# STM8_remote.net
KiCad netlist of a schematic drawn in Altium Designer
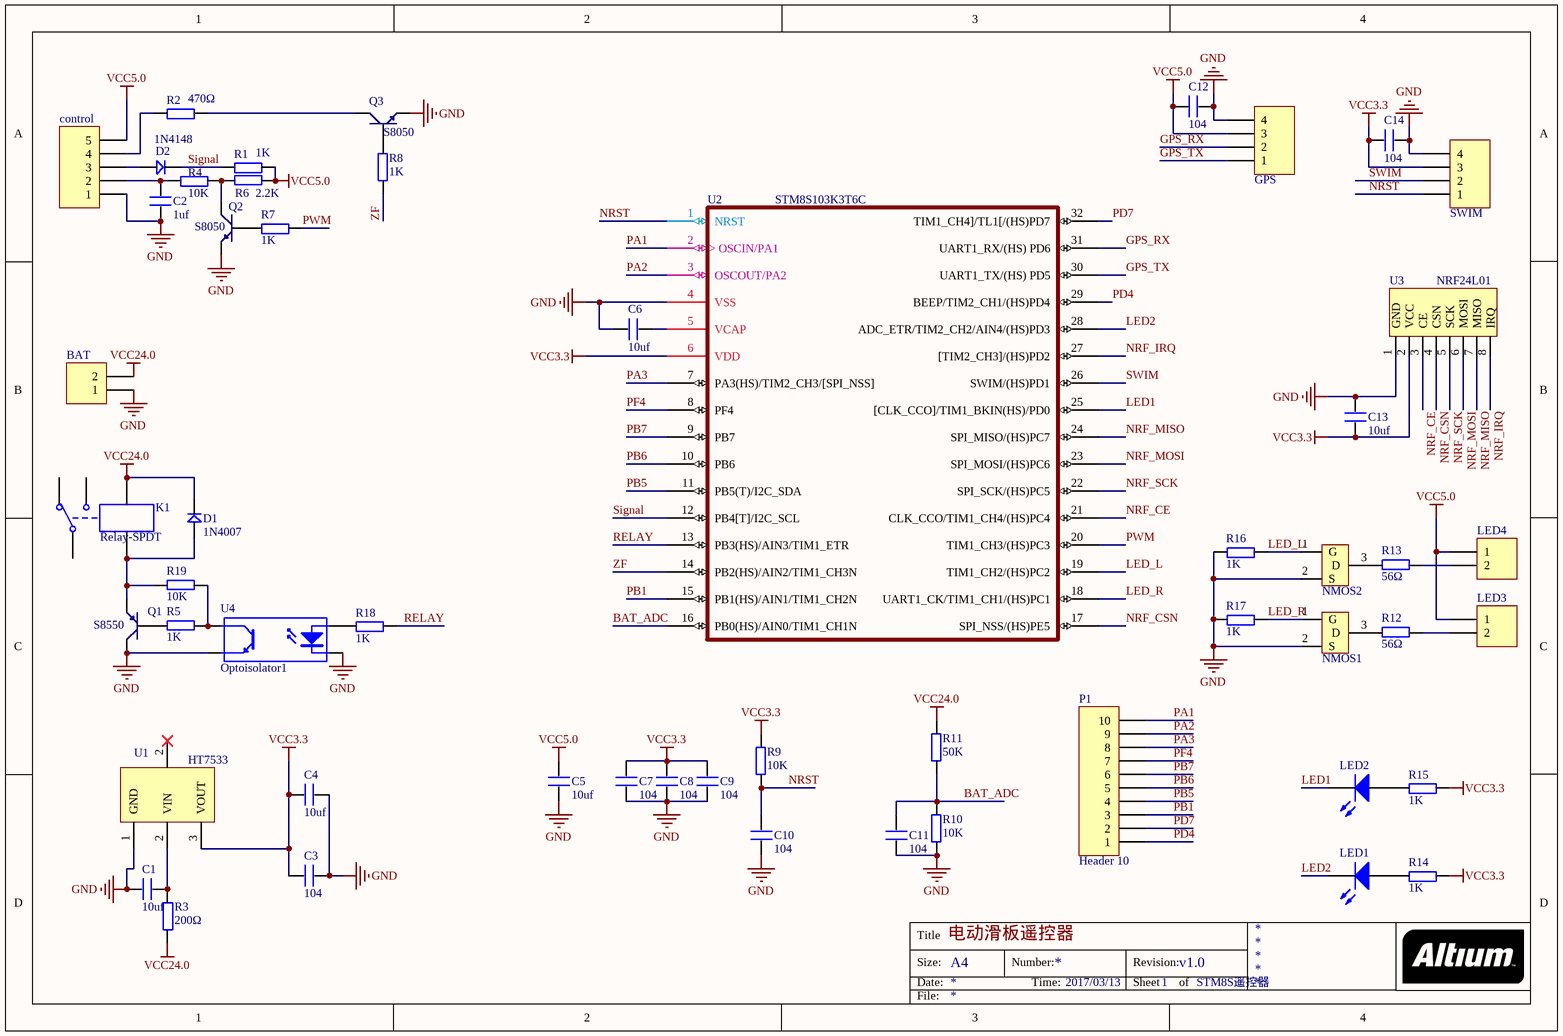
[diagram p0: STM8_remote.SchDoc]

(export (version "E")
  (design (tool "Eeschema 10.0.6"))
  (components
    (comp (ref "BAT")
      (value "Header 2")
      (footprint "HDR1X2")
      (description "Header, 2-Pin")
      (fields (field (name "PUBLISHER") "Altium Limited"))
      (libsource (lib "") (part "Header 2_1"))
    )
    (comp (ref "C1") (value "10uf") (footprint "tantalum capacitors") (libsource (lib "EXPLORER") (part "C")))
    (comp (ref "C2") (value "1uf") (footprint "0603P") (libsource (lib "EXPLORER") (part "C")))
    (comp (ref "C3") (value "104") (footprint "0603P") (libsource (lib "EXPLORER") (part "C")))
    (comp (ref "C4") (value "10uf") (footprint "tantalum capacitors") (libsource (lib "EXPLORER") (part "C")))
    (comp (ref "C5") (value "10uf") (footprint "tantalum capacitors") (libsource (lib "EXPLORER") (part "C")))
    (comp (ref "C6") (value "10uf") (footprint "0805") (libsource (lib "EXPLORER") (part "C")))
    (comp (ref "C7") (value "104") (footprint "0603P") (libsource (lib "EXPLORER") (part "C")))
    (comp (ref "C8") (value "104") (footprint "0603P") (libsource (lib "EXPLORER") (part "C")))
    (comp (ref "C9") (value "104") (footprint "0603P") (libsource (lib "EXPLORER") (part "C")))
    (comp (ref "C10") (value "104") (footprint "0603P") (libsource (lib "EXPLORER") (part "C")))
    (comp (ref "C11") (value "104") (footprint "0603P") (libsource (lib "EXPLORER") (part "C")))
    (comp (ref "C12") (value "104") (footprint "0603P") (libsource (lib "EXPLORER") (part "C")))
    (comp (ref "C13")
      (value "10uf")
      (footprint "tantalum capacitors")
      (libsource (lib "EXPLORER") (part "C"))
    )
    (comp (ref "C14") (value "104") (footprint "0603P") (libsource (lib "EXPLORER") (part "C")))
    (comp (ref "control")
      (value "Header 5")
      (footprint "HDR1X5")
      (description "Header, 5-Pin")
      (fields (field (name "PUBLISHER") "Altium Limited"))
      (libsource (lib "Miscellaneous Connectors") (part "Header 5"))
    )
    (comp (ref "D1") (value "1N4007") (footprint "DIODE_3*5.3") (libsource (lib "EXPLORER") (part "D")))
    (comp (ref "D2") (value "1N4148") (footprint "0603P") (libsource (lib "EXPLORER") (part "D")))
    (comp (ref "GPS")
      (value "Header 4")
      (footprint "HDR1X4")
      (description "Header, 4-Pin")
      (fields (field (name "PUBLISHER") "Altium Limited"))
      (libsource (lib "EXPLORER") (part "Header 4"))
    )
    (comp (ref "K1")
      (value "Relay-SPDT")
      (footprint "RELAY")
      (description "Single-Pole Dual-Throw Relay")
      (fields (field (name "PUBLISHER") "Altium Limited"))
      (libsource (lib "Miscellaneous Devices") (part "Relay-SPDT"))
    )
    (comp (ref "LED1")
      (value "LED1")
      (footprint "SMDLED")
      (description "Typical RED, GREEN, YELLOW, AMBER GaAs LED")
      (fields (field (name "PUBLISHER") "Altium Limited"))
      (libsource (lib "EXPLORER") (part "LED2"))
    )
    (comp (ref "LED2")
      (value "LED1")
      (footprint "SMDLED")
      (description "Typical RED, GREEN, YELLOW, AMBER GaAs LED")
      (fields (field (name "PUBLISHER") "Altium Limited"))
      (libsource (lib "EXPLORER") (part "LED2"))
    )
    (comp (ref "LED3")
      (value "Header 2")
      (footprint "HDR1X2")
      (description "Header, 2-Pin")
      (fields (field (name "PUBLISHER") "Altium Limited"))
      (libsource (lib "Miscellaneous Connectors") (part "Header 2"))
    )
    (comp (ref "LED4")
      (value "Header 2")
      (footprint "HDR1X2")
      (description "Header, 2-Pin")
      (fields (field (name "PUBLISHER") "Altium Limited"))
      (libsource (lib "Miscellaneous Connectors") (part "Header 2"))
    )
    (comp (ref "NMOS1")
      (value "SI2301")
      (footprint "SO-G3/C2.5")
      (description "IRLML6401/SI2301")
      (libsource (lib "EXPLORER") (part "MOS-P"))
    )
    (comp (ref "NMOS2")
      (value "SI2301")
      (footprint "SO-G3/C2.5")
      (description "IRLML6401/SI2301")
      (libsource (lib "EXPLORER") (part "MOS-P"))
    )
    (comp (ref "P1")
      (value "Header 10")
      (footprint "HDR1X10")
      (description "Header, 10-Pin")
      (fields (field (name "PUBLISHER") "Altium Limited"))
      (libsource (lib "Miscellaneous Connectors") (part "Header 10"))
    )
    (comp (ref "Q1")
      (value "S8550")
      (footprint "SOT-23R")
      (description "8550/BCW68")
      (libsource (lib "EXPLORER") (part "PNP"))
    )
    (comp (ref "Q2")
      (value "S8050")
      (footprint "SOT-23R")
      (description "8050/BCW846/BCW847")
      (libsource (lib "EXPLORER") (part "NPN"))
    )
    (comp (ref "Q3")
      (value "S8050")
      (footprint "SOT-23R")
      (description "8050/BCW846/BCW847")
      (libsource (lib "EXPLORER") (part "NPN"))
    )
    (comp (ref "R1") (value "1K") (footprint "0603P") (libsource (lib "EXPLORER") (part "R")))
    (comp (ref "R2") (value "470Ω") (footprint "0603P") (libsource (lib "EXPLORER") (part "R")))
    (comp (ref "R3") (value "200Ω") (footprint "0603P") (libsource (lib "EXPLORER") (part "R")))
    (comp (ref "R4") (value "10K") (footprint "0603P") (libsource (lib "EXPLORER") (part "R")))
    (comp (ref "R5") (value "1K") (footprint "0603P") (libsource (lib "EXPLORER") (part "R")))
    (comp (ref "R6") (value "2.2K") (footprint "0603P") (libsource (lib "EXPLORER") (part "R")))
    (comp (ref "R7") (value "1K") (footprint "0603P") (libsource (lib "EXPLORER") (part "R")))
    (comp (ref "R8") (value "1K") (footprint "0603P") (libsource (lib "EXPLORER") (part "R")))
    (comp (ref "R9") (value "10K") (footprint "0603P") (libsource (lib "EXPLORER") (part "R")))
    (comp (ref "R10") (value "10K") (footprint "0603P") (libsource (lib "EXPLORER") (part "R")))
    (comp (ref "R11") (value "50K") (footprint "0603P") (libsource (lib "EXPLORER") (part "R")))
    (comp (ref "R12") (value "56Ω") (footprint "0805") (libsource (lib "EXPLORER") (part "R")))
    (comp (ref "R13") (value "56Ω") (footprint "0805") (libsource (lib "EXPLORER") (part "R")))
    (comp (ref "R14") (value "1K") (footprint "0603P") (libsource (lib "EXPLORER") (part "R")))
    (comp (ref "R15") (value "1K") (footprint "0603P") (libsource (lib "EXPLORER") (part "R")))
    (comp (ref "R16") (value "1K") (footprint "0603P") (libsource (lib "EXPLORER") (part "R")))
    (comp (ref "R17") (value "1K") (footprint "0603P") (libsource (lib "EXPLORER") (part "R")))
    (comp (ref "R18") (value "1K") (footprint "0603P") (libsource (lib "EXPLORER") (part "R")))
    (comp (ref "R19") (value "10K") (footprint "0603P") (libsource (lib "EXPLORER") (part "R")))
    (comp (ref "SWIM")
      (value "Header 4")
      (footprint "HDR1X4")
      (description "Header, 4-Pin")
      (fields (field (name "PUBLISHER") "Altium Limited"))
      (libsource (lib "EXPLORER") (part "Header 4"))
    )
    (comp (ref "U1") (value "HT7533") (footprint "SOT-89") (libsource (lib "*") (part "HT75xx")))
    (comp (ref "U2")
      (value "STM8S103K3T6C")
      (footprint "TQFP32")
      (description "ST 8-bit  Microcontroller")
      (libsource (lib "STMicrocontroller 8") (part "STM8S103K3T6"))
    )
    (comp (ref "U3") (value "NRF24L01") (footprint "NRF24L01") (libsource (lib "EXPLORER") (part "NRF24L01")))
    (comp (ref "U4")
      (value "Optoisolator1")
      (footprint "DIP-4")
      (description "4-Pin Phototransistor Optocoupler")
      (fields (field (name "PUBLISHER") "Altium Limited"))
      (libsource (lib "Miscellaneous Devices") (part "Optoisolator1"))
    )
  )
  (nets
    (net (code "1") (name "/BAT_ADC") (class "Default")
      (node (ref "C11") (pin "2") (pintype "passive"))
      (node (ref "R10") (pin "1") (pintype "passive"))
      (node (ref "R11") (pin "2") (pintype "passive"))
      (node (ref "U2") (pin "16") (pinfunction "PB0(HS)/AIN0/TIM1_CH1N_16") (pintype "bidirectional"))
    )
    (net (code "2") (name "/GPS_RX") (class "Default")
      (node (ref "GPS") (pin "2") (pinfunction "2_2") (pintype "passive"))
      (node (ref "U2") (pin "31") (pinfunction "UART1_RX/(HS)_PD6_31") (pintype "bidirectional"))
    )
    (net (code "3") (name "/GPS_TX") (class "Default")
      (node (ref "GPS") (pin "1") (pinfunction "1_1") (pintype "passive"))
      (node (ref "U2") (pin "30") (pinfunction "UART1_TX/(HS)_PD5_30") (pintype "bidirectional"))
    )
    (net (code "4") (name "/LED1") (class "Default")
      (node (ref "LED2") (pin "2") (pinfunction "K_2") (pintype "passive"))
      (node (ref "U2") (pin "25") (pinfunction "[CLK_CCO]/TIM1_BKIN(HS)/PD0_25") (pintype "bidirectional"))
    )
    (net (code "5") (name "/LED2") (class "Default")
      (node (ref "LED1") (pin "2") (pinfunction "K_2") (pintype "passive"))
      (node (ref "U2") (pin "28") (pinfunction "ADC_ETR/TIM2_CH2/AIN4/(HS)PD3_28") (pintype "bidirectional"))
    )
    (net (code "6") (name "/LED_L") (class "Default")
      (node (ref "NMOS2") (pin "1") (pinfunction "G_1") (pintype "passive"))
      (node (ref "R16") (pin "2") (pintype "passive"))
      (node (ref "U2") (pin "19") (pinfunction "TIM1_CH2/(HS)PC2_19") (pintype "bidirectional"))
    )
    (net (code "7") (name "/LED_R") (class "Default")
      (node (ref "NMOS1") (pin "1") (pinfunction "G_1") (pintype "passive"))
      (node (ref "R17") (pin "2") (pintype "passive"))
      (node (ref "U2") (pin "18") (pinfunction "UART1_CK/TIM1_CH1/(HS)PC1_18") (pintype "bidirectional"))
    )
    (net (code "8") (name "/NRF_CE") (class "Default")
      (node (ref "U2") (pin "21") (pinfunction "CLK_CCO/TIM1_CH4/(HS)PC4_21") (pintype "bidirectional"))
      (node (ref "U3") (pin "3") (pinfunction "CE_3") (pintype "passive"))
    )
    (net (code "9") (name "/NRF_CSN") (class "Default")
      (node (ref "U2") (pin "17") (pinfunction "SPI_NSS/(HS)PE5_17") (pintype "bidirectional"))
      (node (ref "U3") (pin "4") (pinfunction "CSN_4") (pintype "passive"))
    )
    (net (code "10") (name "/NRF_IRQ") (class "Default")
      (node (ref "U2") (pin "27") (pinfunction "[TIM2_CH3]/(HS)PD2_27") (pintype "bidirectional"))
      (node (ref "U3") (pin "8") (pinfunction "IRQ_8") (pintype "passive"))
    )
    (net (code "11") (name "/NRF_MISO") (class "Default")
      (node (ref "U2") (pin "24") (pinfunction "SPI_MISO/(HS)PC7_24") (pintype "bidirectional"))
      (node (ref "U3") (pin "7") (pinfunction "MISO_7") (pintype "passive"))
    )
    (net (code "12") (name "/NRF_MOSI") (class "Default")
      (node (ref "U2") (pin "23") (pinfunction "SPI_MOSI/(HS)PC6_23") (pintype "bidirectional"))
      (node (ref "U3") (pin "6") (pinfunction "MOSI_6") (pintype "passive"))
    )
    (net (code "13") (name "/NRF_SCK") (class "Default")
      (node (ref "U2") (pin "22") (pinfunction "SPI_SCK/(HS)PC5_22") (pintype "bidirectional"))
      (node (ref "U3") (pin "5") (pinfunction "SCK_5") (pintype "passive"))
    )
    (net (code "14") (name "/NRST") (class "Default")
      (node (ref "C10") (pin "2") (pintype "passive"))
      (node (ref "R9") (pin "2") (pintype "passive"))
      (node (ref "SWIM") (pin "1") (pinfunction "1_1") (pintype "passive"))
      (node (ref "U2") (pin "1") (pinfunction "NRST_1") (pintype "bidirectional"))
    )
    (net (code "15") (name "/PA1") (class "Default")
      (node (ref "P1") (pin "10") (pinfunction "10_10") (pintype "passive"))
      (node (ref "U2") (pin "2") (pinfunction "OSCIN/PA1_2") (pintype "bidirectional"))
    )
    (net (code "16") (name "/PA2") (class "Default")
      (node (ref "P1") (pin "9") (pinfunction "9_9") (pintype "passive"))
      (node (ref "U2") (pin "3") (pinfunction "OSCOUT/PA2_3") (pintype "bidirectional"))
    )
    (net (code "17") (name "/PA3") (class "Default")
      (node (ref "P1") (pin "8") (pinfunction "8_8") (pintype "passive"))
      (node (ref "U2") (pin "7") (pinfunction "PA3(HS)/TIM2_CH3/[SPI_NSS]_7") (pintype "bidirectional"))
    )
    (net (code "18") (name "/PB1") (class "Default")
      (node (ref "P1") (pin "3") (pinfunction "3_3") (pintype "passive"))
      (node (ref "U2") (pin "15") (pinfunction "PB1(HS)/AIN1/TIM1_CH2N_15") (pintype "bidirectional"))
    )
    (net (code "19") (name "/PB5") (class "Default")
      (node (ref "P1") (pin "4") (pinfunction "4_4") (pintype "passive"))
      (node (ref "U2") (pin "11") (pinfunction "PB5(T)/I2C_SDA_11") (pintype "bidirectional"))
    )
    (net (code "20") (name "/PB6") (class "Default")
      (node (ref "P1") (pin "5") (pinfunction "5_5") (pintype "passive"))
      (node (ref "U2") (pin "10") (pinfunction "PB6_10") (pintype "bidirectional"))
    )
    (net (code "21") (name "/PB7") (class "Default")
      (node (ref "P1") (pin "6") (pinfunction "6_6") (pintype "passive"))
      (node (ref "U2") (pin "9") (pinfunction "PB7_9") (pintype "bidirectional"))
    )
    (net (code "22") (name "/PD4") (class "Default")
      (node (ref "P1") (pin "1") (pinfunction "1_1") (pintype "passive"))
      (node (ref "U2") (pin "29") (pinfunction "BEEP/TIM2_CH1/(HS)PD4_29") (pintype "bidirectional"))
    )
    (net (code "23") (name "/PD7") (class "Default")
      (node (ref "P1") (pin "2") (pinfunction "2_2") (pintype "passive"))
      (node (ref "U2") (pin "32") (pinfunction "TIM1_CH4]/TL1[/(HS)PD7_32") (pintype "bidirectional"))
    )
    (net (code "24") (name "/PF4") (class "Default")
      (node (ref "P1") (pin "7") (pinfunction "7_7") (pintype "passive"))
      (node (ref "U2") (pin "8") (pinfunction "PF4_8") (pintype "bidirectional"))
    )
    (net (code "25") (name "/PWM") (class "Default")
      (node (ref "R7") (pin "2") (pintype "passive"))
      (node (ref "U2") (pin "20") (pinfunction "TIM1_CH3/(HS)PC3_20") (pintype "bidirectional"))
    )
    (net (code "26") (name "/RELAY") (class "Default")
      (node (ref "R18") (pin "2") (pintype "passive"))
      (node (ref "U2") (pin "13") (pinfunction "PB3(HS)/AIN3/TIM1_ETR_13") (pintype "bidirectional"))
    )
    (net (code "27") (name "/SWIM") (class "Default")
      (node (ref "SWIM") (pin "2") (pinfunction "2_2") (pintype "passive"))
      (node (ref "U2") (pin "26") (pinfunction "SWIM/(HS)PD1_26") (pintype "bidirectional"))
    )
    (net (code "28") (name "/Signal") (class "Default")
      (node (ref "D2") (pin "2") (pintype "passive"))
      (node (ref "R1") (pin "1") (pintype "passive"))
      (node (ref "U2") (pin "12") (pinfunction "PB4[T]/I2C_SCL_12") (pintype "bidirectional"))
    )
    (net (code "29") (name "/ZF") (class "Default")
      (node (ref "R8") (pin "2") (pintype "passive"))
      (node (ref "U2") (pin "14") (pinfunction "PB2(HS)/AIN2/TIM1_CH3N_14") (pintype "bidirectional"))
    )
    (net (code "30") (name "GND") (class "Default")
      (node (ref "BAT") (pin "1") (pinfunction "1_1") (pintype "passive"))
      (node (ref "C1") (pin "1") (pintype "passive"))
      (node (ref "C10") (pin "1") (pintype "passive"))
      (node (ref "C11") (pin "1") (pintype "passive"))
      (node (ref "C12") (pin "2") (pintype "passive"))
      (node (ref "C13") (pin "1") (pintype "passive"))
      (node (ref "C14") (pin "2") (pintype "passive"))
      (node (ref "C2") (pin "1") (pintype "passive"))
      (node (ref "C3") (pin "1") (pintype "passive"))
      (node (ref "C4") (pin "1") (pintype "passive"))
      (node (ref "C5") (pin "1") (pintype "passive"))
      (node (ref "C6") (pin "1") (pintype "passive"))
      (node (ref "C7") (pin "1") (pintype "passive"))
      (node (ref "C8") (pin "1") (pintype "passive"))
      (node (ref "C9") (pin "1") (pintype "passive"))
      (node (ref "GPS") (pin "4") (pinfunction "4_4") (pintype "passive"))
      (node (ref "NMOS1") (pin "2") (pinfunction "S_2") (pintype "passive"))
      (node (ref "NMOS2") (pin "2") (pinfunction "S_2") (pintype "passive"))
      (node (ref "Q1") (pin "3") (pinfunction "C_3") (pintype "passive"))
      (node (ref "Q2") (pin "1") (pinfunction "E_1") (pintype "passive"))
      (node (ref "Q3") (pin "1") (pinfunction "E_1") (pintype "passive"))
      (node (ref "R10") (pin "2") (pintype "passive"))
      (node (ref "R16") (pin "1") (pintype "passive"))
      (node (ref "R17") (pin "1") (pintype "passive"))
      (node (ref "SWIM") (pin "4") (pinfunction "4_4") (pintype "passive"))
      (node (ref "U1") (pin "1") (pinfunction "GND_1") (pintype "passive"))
      (node (ref "U2") (pin "4") (pinfunction "VSS_4") (pintype "power_in"))
      (node (ref "U3") (pin "1") (pinfunction "GND_1") (pintype "passive"))
      (node (ref "U4") (pin "2") (pinfunction "K_2") (pintype "passive"))
      (node (ref "U4") (pin "3") (pinfunction "E_3") (pintype "passive"))
      (node (ref "control") (pin "1") (pinfunction "1_1") (pintype "passive"))
    )
    (net (code "31") (name "Net-(C2-Pad2)") (class "Default")
      (node (ref "C2") (pin "2") (pintype "passive"))
      (node (ref "R4") (pin "1") (pintype "passive"))
      (node (ref "control") (pin "2") (pinfunction "2_2") (pintype "passive"))
    )
    (net (code "32") (name "Net-(D2-Pad1)") (class "Default")
      (node (ref "D2") (pin "1") (pintype "passive"))
      (node (ref "control") (pin "3") (pinfunction "3_3") (pintype "passive"))
    )
    (net (code "33") (name "Net-(LED1-A)") (class "Default")
      (node (ref "LED1") (pin "1") (pinfunction "A_1") (pintype "passive"))
      (node (ref "R14") (pin "1") (pintype "passive"))
    )
    (net (code "34") (name "Net-(LED2-A)") (class "Default")
      (node (ref "LED2") (pin "1") (pinfunction "A_1") (pintype "passive"))
      (node (ref "R15") (pin "1") (pintype "passive"))
    )
    (net (code "35") (name "Net-(LED3-Pad2)") (class "Default")
      (node (ref "LED3") (pin "2") (pinfunction "2_2") (pintype "passive"))
      (node (ref "R12") (pin "1") (pintype "passive"))
    )
    (net (code "36") (name "Net-(LED4-Pad2)") (class "Default")
      (node (ref "LED4") (pin "2") (pinfunction "2_2") (pintype "passive"))
      (node (ref "R13") (pin "1") (pintype "passive"))
    )
    (net (code "37") (name "Net-(NMOS1-D)") (class "Default")
      (node (ref "NMOS1") (pin "3") (pinfunction "D_3") (pintype "passive"))
      (node (ref "R12") (pin "2") (pintype "passive"))
    )
    (net (code "38") (name "Net-(NMOS2-D)") (class "Default")
      (node (ref "NMOS2") (pin "3") (pinfunction "D_3") (pintype "passive"))
      (node (ref "R13") (pin "2") (pintype "passive"))
    )
    (net (code "39") (name "Net-(Q1-B)") (class "Default")
      (node (ref "Q1") (pin "2") (pinfunction "B_2") (pintype "passive"))
      (node (ref "R5") (pin "2") (pintype "passive"))
    )
    (net (code "40") (name "Net-(Q1-E)") (class "Default")
      (node (ref "D1") (pin "1") (pintype "passive"))
      (node (ref "K1") (pin "4") (pinfunction "4_4") (pintype "passive"))
      (node (ref "Q1") (pin "1") (pinfunction "E_1") (pintype "passive"))
      (node (ref "R19") (pin "2") (pintype "passive"))
    )
    (net (code "41") (name "Net-(Q2-B)") (class "Default")
      (node (ref "Q2") (pin "2") (pinfunction "B_2") (pintype "passive"))
      (node (ref "R7") (pin "1") (pintype "passive"))
    )
    (net (code "42") (name "Net-(Q2-C)") (class "Default")
      (node (ref "Q2") (pin "3") (pinfunction "C_3") (pintype "passive"))
      (node (ref "R4") (pin "2") (pintype "passive"))
      (node (ref "R6") (pin "2") (pintype "passive"))
    )
    (net (code "43") (name "Net-(Q3-B)") (class "Default")
      (node (ref "Q3") (pin "2") (pinfunction "B_2") (pintype "passive"))
      (node (ref "R8") (pin "1") (pintype "passive"))
    )
    (net (code "44") (name "Net-(Q3-C)") (class "Default")
      (node (ref "Q3") (pin "3") (pinfunction "C_3") (pintype "passive"))
      (node (ref "R2") (pin "2") (pintype "passive"))
    )
    (net (code "45") (name "Net-(R2-Pad1)") (class "Default")
      (node (ref "R2") (pin "1") (pintype "passive"))
      (node (ref "control") (pin "4") (pinfunction "4_4") (pintype "passive"))
    )
    (net (code "46") (name "Net-(U1-VIN)") (class "Default")
      (node (ref "C1") (pin "2") (pintype "passive"))
      (node (ref "R3") (pin "2") (pintype "passive"))
      (node (ref "U1") (pin "2") (pinfunction "VIN_2") (pintype "passive"))
    )
    (net (code "47") (name "Net-(U2-VCAP)") (class "Default")
      (node (ref "C6") (pin "2") (pintype "passive"))
      (node (ref "U2") (pin "5") (pinfunction "VCAP_5") (pintype "power_in"))
    )
    (net (code "48") (name "Net-(U4-A)") (class "Default")
      (node (ref "R18") (pin "1") (pintype "passive"))
      (node (ref "U4") (pin "1") (pinfunction "A_1") (pintype "passive"))
    )
    (net (code "49") (name "Net-(U4-C)") (class "Default")
      (node (ref "R19") (pin "1") (pintype "passive"))
      (node (ref "R5") (pin "1") (pintype "passive"))
      (node (ref "U4") (pin "4") (pinfunction "C_4") (pintype "passive"))
    )
    (net (code "50") (name "VCC3.3") (class "Default")
      (node (ref "C13") (pin "2") (pintype "passive"))
      (node (ref "C14") (pin "1") (pintype "passive"))
      (node (ref "C3") (pin "2") (pintype "passive"))
      (node (ref "C4") (pin "2") (pintype "passive"))
      (node (ref "C7") (pin "2") (pintype "passive"))
      (node (ref "C8") (pin "2") (pintype "passive"))
      (node (ref "C9") (pin "2") (pintype "passive"))
      (node (ref "R14") (pin "2") (pintype "passive"))
      (node (ref "R15") (pin "2") (pintype "passive"))
      (node (ref "R9") (pin "1") (pintype "passive"))
      (node (ref "SWIM") (pin "3") (pinfunction "3_3") (pintype "passive"))
      (node (ref "U1") (pin "3") (pinfunction "VOUT_3") (pintype "passive"))
      (node (ref "U2") (pin "6") (pinfunction "VDD_6") (pintype "power_in"))
      (node (ref "U3") (pin "2") (pinfunction "VCC_2") (pintype "passive"))
    )
    (net (code "51") (name "VCC5.0") (class "Default")
      (node (ref "C12") (pin "1") (pintype "passive"))
      (node (ref "C5") (pin "2") (pintype "passive"))
      (node (ref "GPS") (pin "3") (pinfunction "3_3") (pintype "passive"))
      (node (ref "LED3") (pin "1") (pinfunction "1_1") (pintype "passive"))
      (node (ref "LED4") (pin "1") (pinfunction "1_1") (pintype "passive"))
      (node (ref "R1") (pin "2") (pintype "passive"))
      (node (ref "R6") (pin "1") (pintype "passive"))
      (node (ref "control") (pin "5") (pinfunction "5_5") (pintype "passive"))
    )
    (net (code "52") (name "VCC24.0") (class "Default")
      (node (ref "BAT") (pin "2") (pinfunction "2_2") (pintype "passive"))
      (node (ref "D1") (pin "2") (pintype "passive"))
      (node (ref "K1") (pin "5") (pinfunction "5_5") (pintype "passive"))
      (node (ref "R11") (pin "1") (pintype "passive"))
      (node (ref "R3") (pin "1") (pintype "passive"))
    )
    (net (code "53") (name "unconnected-(K1-Pad1)") (class "Default")
      (node (ref "K1") (pin "1") (pinfunction "1_1") (pintype "passive"))
    )
    (net (code "54") (name "unconnected-(K1-Pad2)") (class "Default")
      (node (ref "K1") (pin "2") (pinfunction "2_2") (pintype "passive"))
    )
    (net (code "55") (name "unconnected-(K1-Pad3)") (class "Default")
      (node (ref "K1") (pin "3") (pinfunction "3_3") (pintype "passive"))
    )
    (net (code "56") (name "unconnected-(U1-VIN-Pad2)") (class "Default")
      (node (ref "U1") (pin "2") (pinfunction "VIN_2") (pintype "passive+no_connect"))
    )
  )
)
